# HPS_IOs.net
KiCad netlist of a schematic drawn in Altium Designer
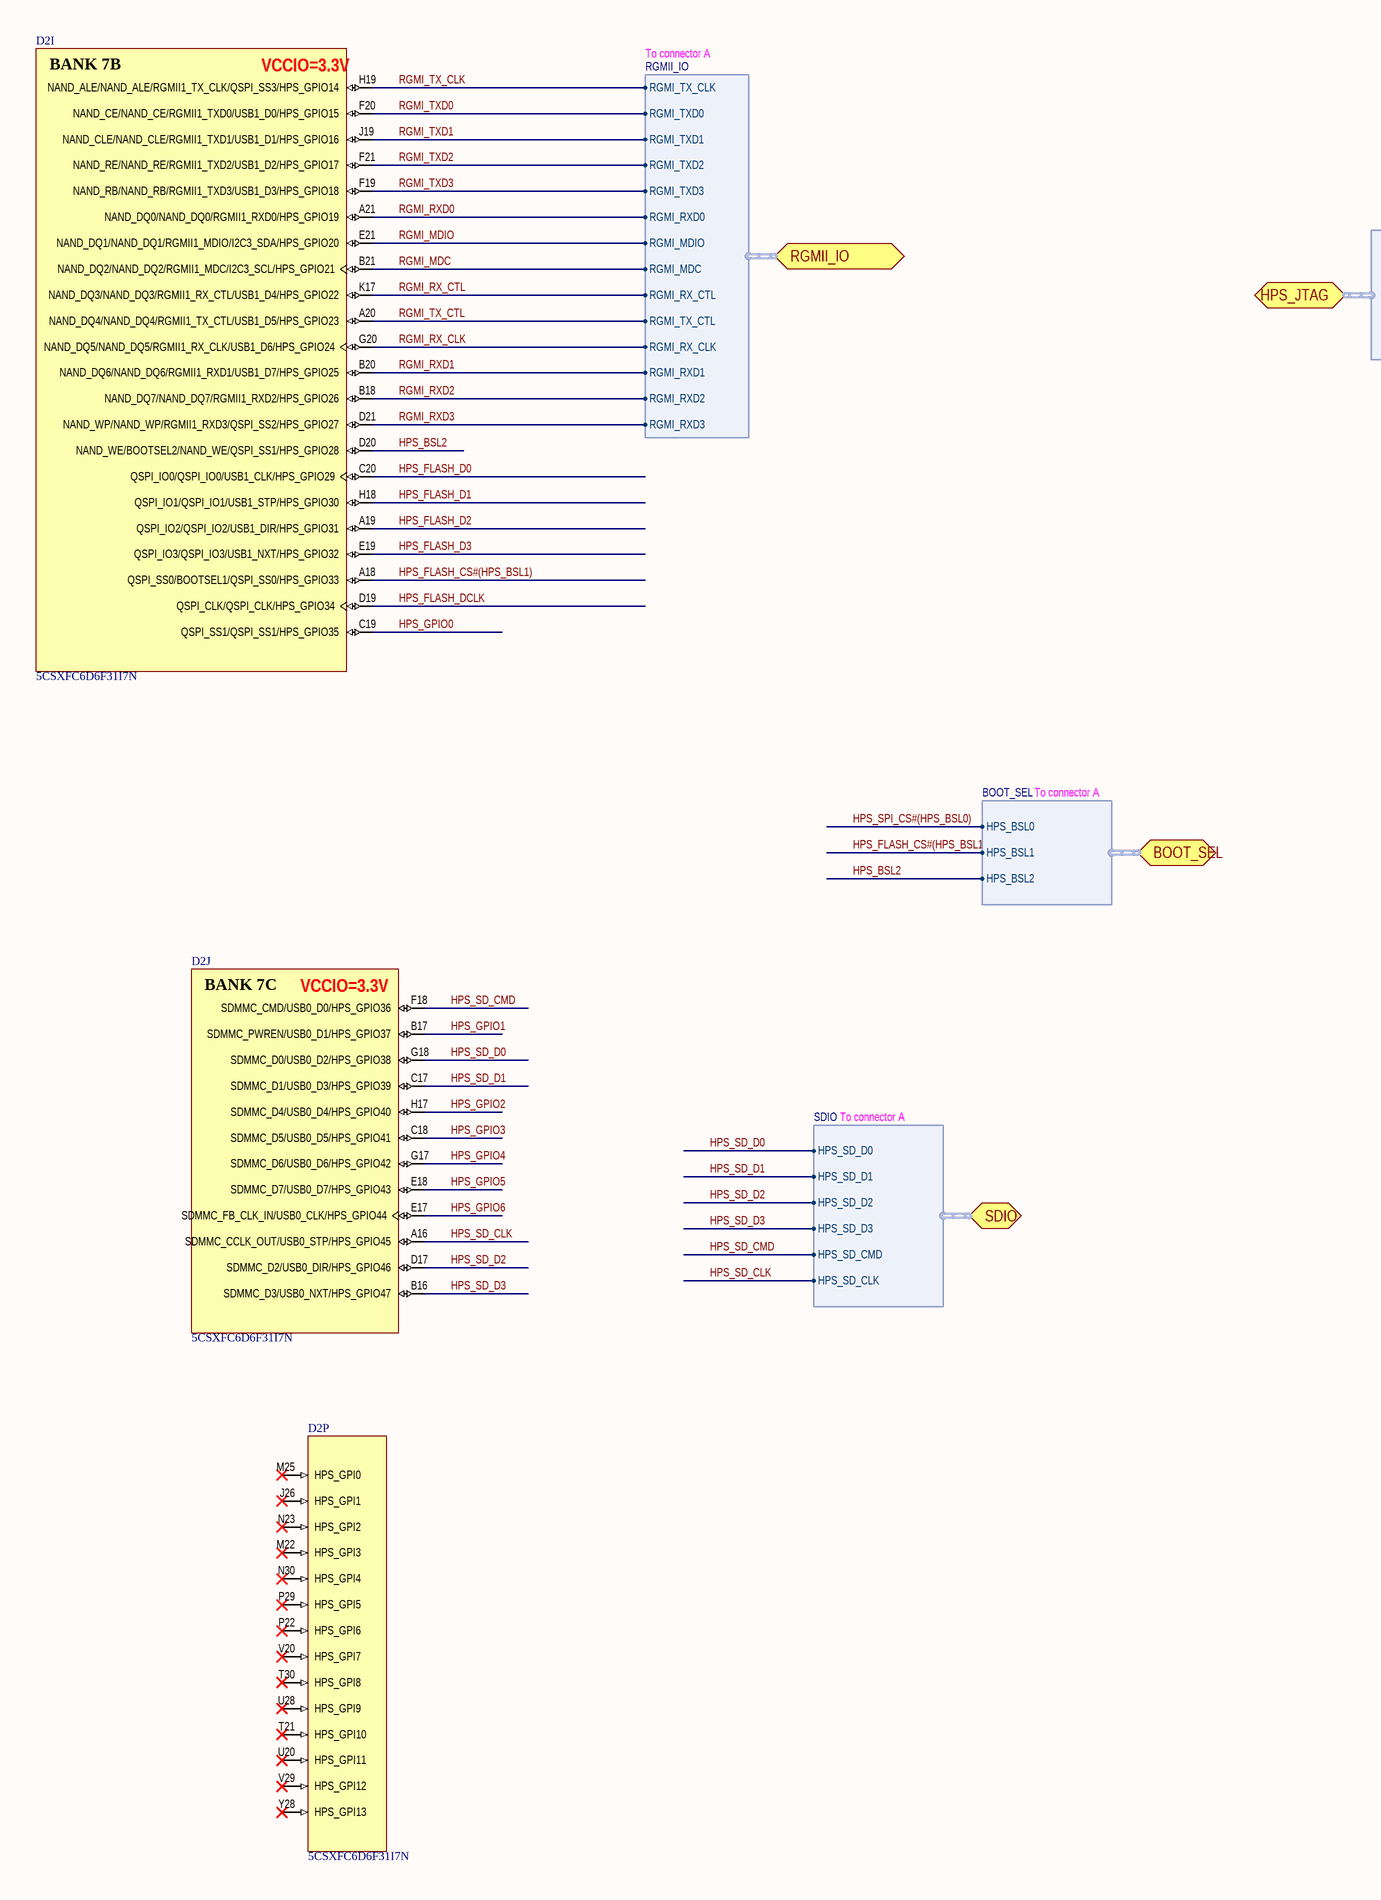
[diagram p0: HPS_IOs.SchDoc, left]
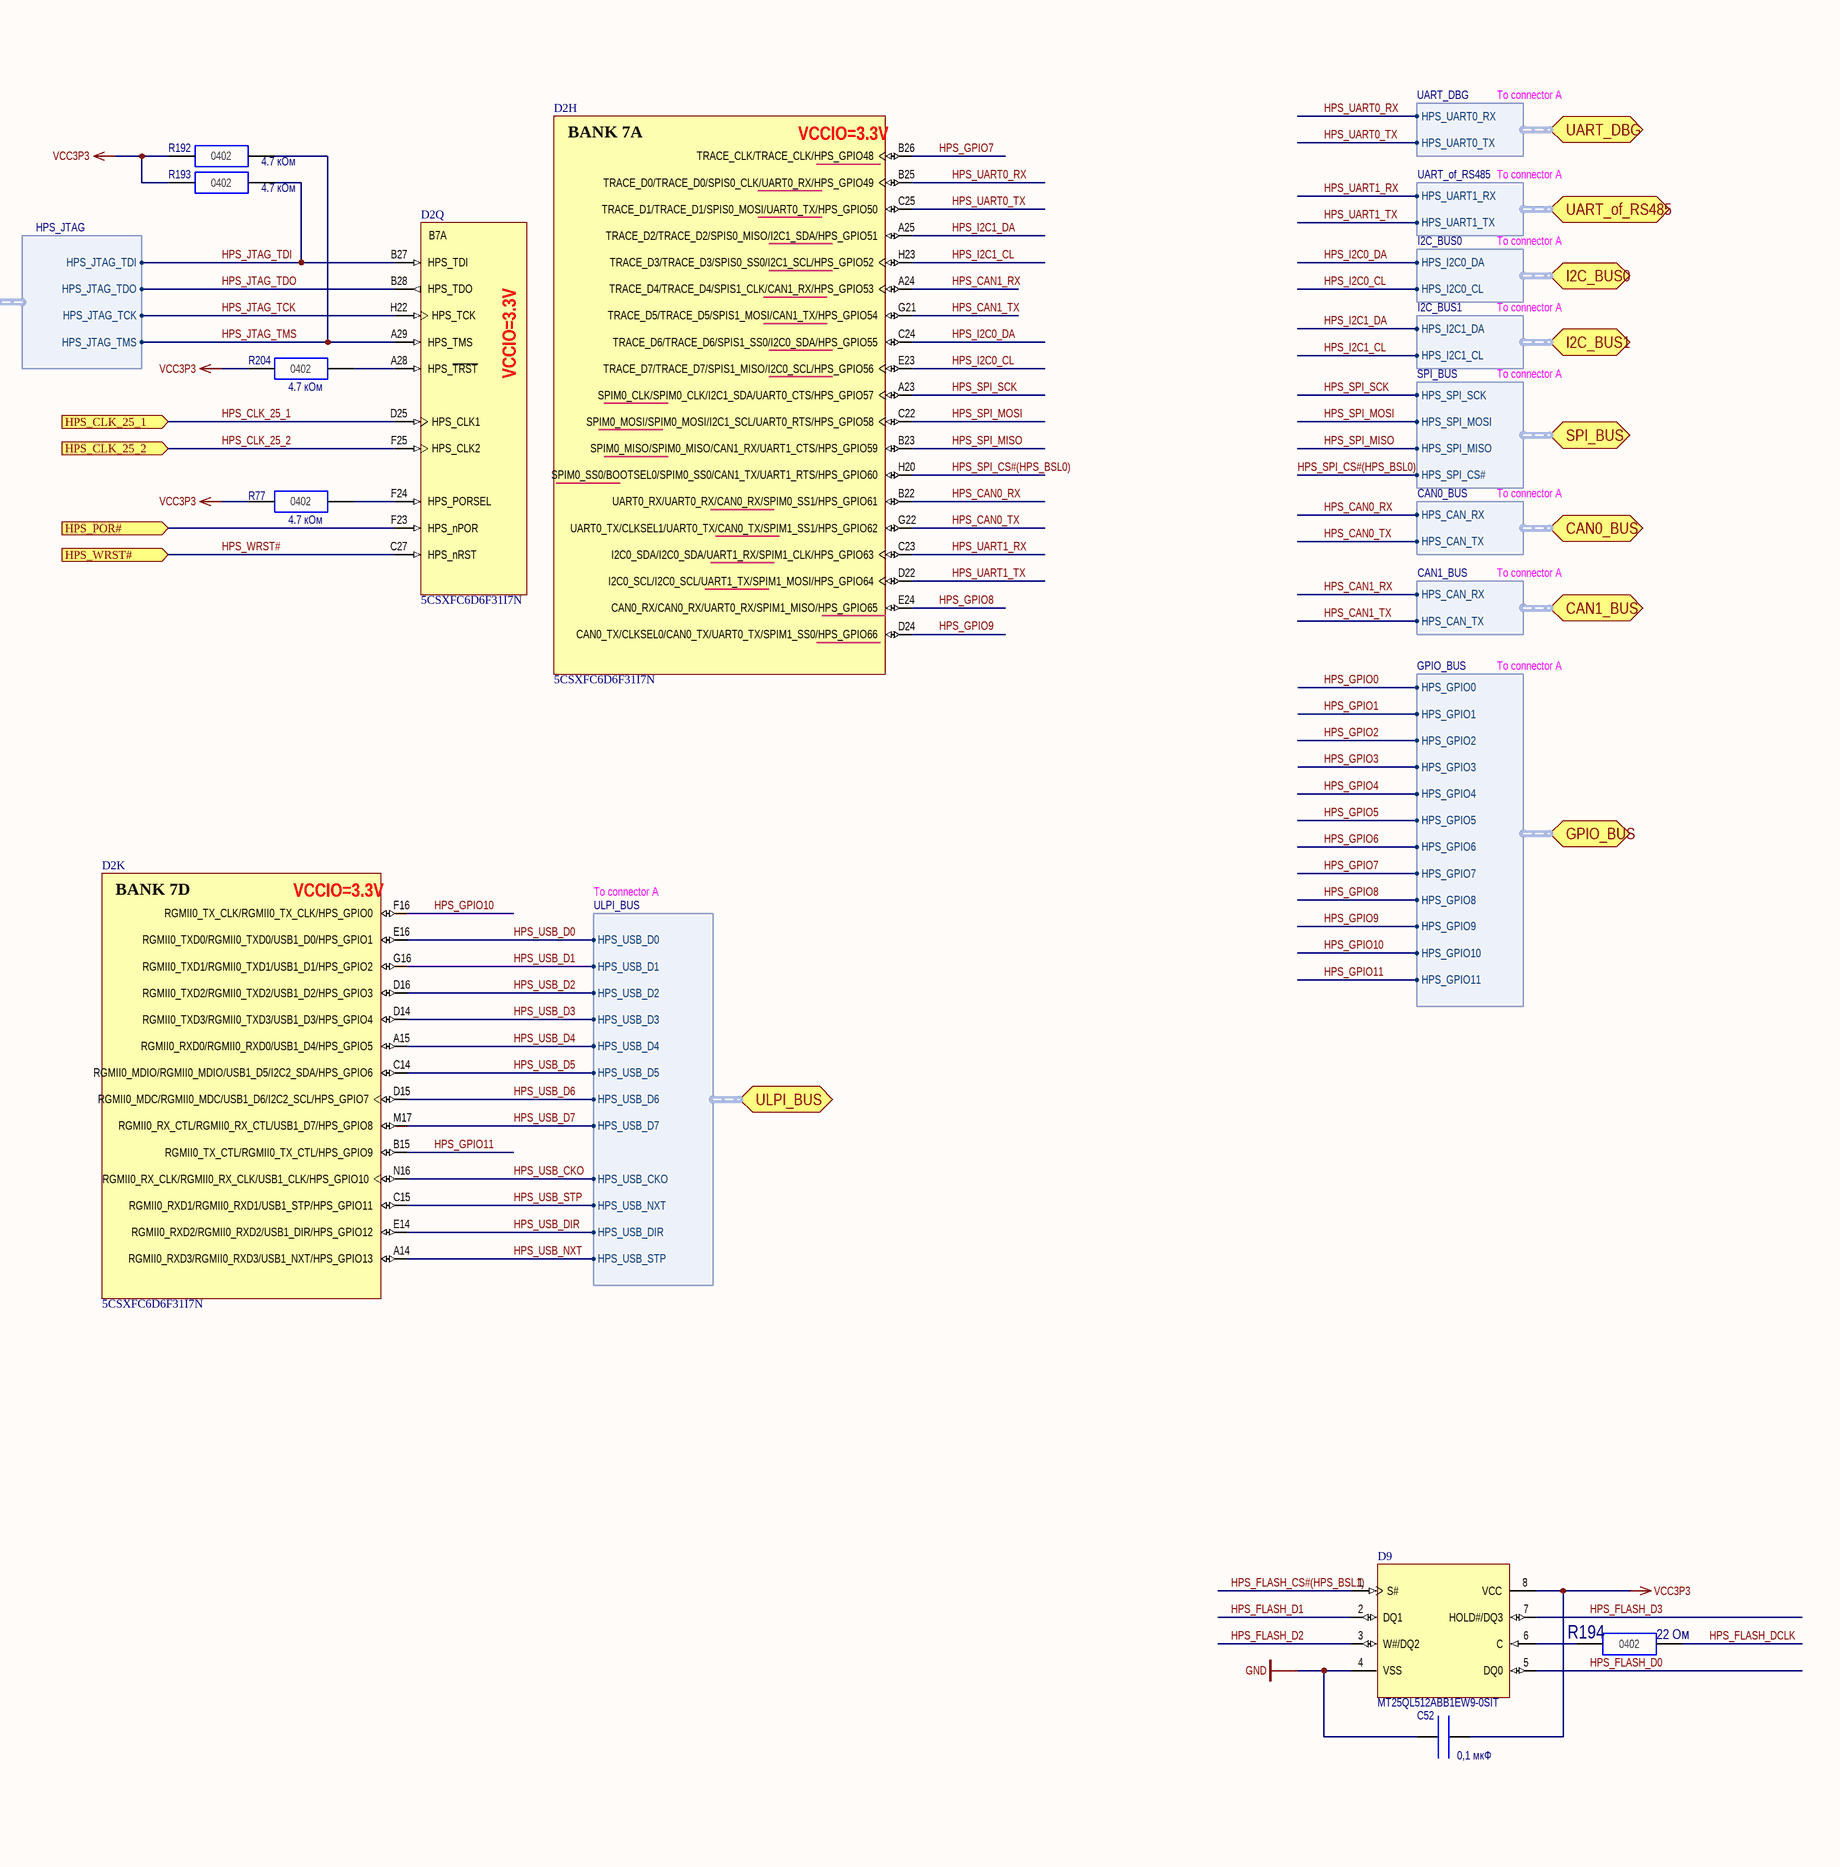
[diagram p1: HPS_IOs.SchDoc, right]

(export (version "E")
  (design (tool "Eeschema 10.0.6"))
  (components
    (comp (ref "C52")
      (value "0,1 мкФ")
      (footprint "CC0402(1005)")
      (description "Чип конденсатор керамический")
      (fields (field (name "Comment") "CC0402-X7R-0,1 мкФ-20%-10В"))
      (libsource (lib "Чип конденсаторы") (part "CC0402-X7R-#-20%-10В"))
    )
    (comp (ref "D2")
      (value "5CSXFC6D6F31I7N")
      (footprint "ALTR-FBGA896_A-200")
      (fields (field (name "MANUFACTURER") "Altera"))
      (libsource (lib "Altera Cyclone V_sd") (part "5CSXFC6D6F31I7N"))
    )
    (comp (ref "D9")
      (value "MT25QL512ABB1EW9-0SIT")
      (footprint "SON127P800X80_HS-9N")
      (fields (field (name "VOLTAGE") "2.7V-3.6V ") (field (name "MANUFACTURER") "Micron"))
      (libsource (lib "SD_IC") (part "MT25QL512ABB1EW9-0SIT"))
    )
    (comp (ref "R77")
      (value "4.7 кОм")
      (footprint "CR0402(1005)_OCT")
      (description "Чип резистор")
      (fields (field (name "TOLERANCE") "5%") (field (name "Comment") "CR0402-4.7 кОм-±5%"))
      (libsource (lib "Резисторы") (part "CR0402-#-±5%"))
    )
    (comp (ref "R192")
      (value "4.7 кОм")
      (footprint "CR0402(1005)")
      (description "Чип резистор")
      (fields (field (name "TOLERANCE") "5%") (field (name "Comment") "CR0402-4.7 кОм-±5%"))
      (libsource (lib "Резисторы") (part "CR0402-#-±5%"))
    )
    (comp (ref "R193")
      (value "4.7 кОм")
      (footprint "CR0402(1005)_OCT")
      (description "Чип резистор")
      (fields (field (name "TOLERANCE") "5%") (field (name "Comment") "CR0402-4.7 кОм-±5%"))
      (libsource (lib "Резисторы") (part "CR0402-#-±5%"))
    )
    (comp (ref "R194")
      (value "22 Ом")
      (footprint "CR0402(1005)")
      (description "Чип резистор")
      (fields (field (name "TOLERANCE") "5%") (field (name "Comment") "CR0402-22 Ом-±5%"))
      (libsource (lib "Чип резисторы") (part "CR0402-#-±5%"))
    )
    (comp (ref "R204")
      (value "4.7 кОм")
      (footprint "CR0402(1005)")
      (description "Чип резистор")
      (fields (field (name "TOLERANCE") "5%") (field (name "Comment") "CR0402-4.7 кОм-±5%"))
      (libsource (lib "Резисторы") (part "CR0402-#-±5%"))
    )
  )
  (nets
    (net (code "14") (name "/HPS_BSL2") (class "Default")
      (node (ref "D2") (pin "D20") (pinfunction "NAND_WE/BOOTSEL2/NAND_WE/QSPI_SS1/HPS_GPIO28_D20") (pintype "bidirectional"))
    )
    (net (code "15") (name "/HPS_CAN0_RX") (class "Default")
      (node (ref "D2") (pin "B22") (pinfunction "UART0_RX/UART0_RX/CAN0_RX/SPIM0_SS1/HPS_GPIO61_B22") (pintype "bidirectional"))
    )
    (net (code "16") (name "/HPS_CAN0_TX") (class "Default")
      (node (ref "D2") (pin "G22") (pinfunction "UART0_TX/CLKSEL1/UART0_TX/CAN0_TX/SPIM1_SS1/HPS_GPIO62_G22") (pintype "bidirectional"))
    )
    (net (code "17") (name "/HPS_CAN1_RX") (class "Default")
      (node (ref "D2") (pin "A24") (pinfunction "TRACE_D4/TRACE_D4/SPIS1_CLK/CAN1_RX/HPS_GPIO53_A24") (pintype "bidirectional"))
    )
    (net (code "18") (name "/HPS_CAN1_TX") (class "Default")
      (node (ref "D2") (pin "G21") (pinfunction "TRACE_D5/TRACE_D5/SPIS1_MOSI/CAN1_TX/HPS_GPIO54_G21") (pintype "bidirectional"))
    )
    (net (code "19") (name "/HPS_CLK_25_1") (class "Default")
      (node (ref "D2") (pin "D25") (pinfunction "HPS_CLK1_D25") (pintype "input"))
    )
    (net (code "20") (name "/HPS_CLK_25_2") (class "Default")
      (node (ref "D2") (pin "F25") (pinfunction "HPS_CLK2_F25") (pintype "input"))
    )
    (net (code "21") (name "/HPS_FLASH_CS#(HPS_BSL1)") (class "Default")
      (node (ref "D2") (pin "A18") (pinfunction "QSPI_SS0/BOOTSEL1/QSPI_SS0/HPS_GPIO33_A18") (pintype "bidirectional"))
      (node (ref "D9") (pin "1") (pinfunction "S#_1") (pintype "input"))
    )
    (net (code "22") (name "/HPS_FLASH_D0") (class "Default")
      (node (ref "D2") (pin "C20") (pinfunction "QSPI_IO0/QSPI_IO0/USB1_CLK/HPS_GPIO29_C20") (pintype "bidirectional"))
      (node (ref "D9") (pin "5") (pinfunction "DQ0_5") (pintype "bidirectional"))
    )
    (net (code "23") (name "/HPS_FLASH_D1") (class "Default")
      (node (ref "D2") (pin "H18") (pinfunction "QSPI_IO1/QSPI_IO1/USB1_STP/HPS_GPIO30_H18") (pintype "bidirectional"))
      (node (ref "D9") (pin "2") (pinfunction "DQ1_2") (pintype "bidirectional"))
    )
    (net (code "24") (name "/HPS_FLASH_D2") (class "Default")
      (node (ref "D2") (pin "A19") (pinfunction "QSPI_IO2/QSPI_IO2/USB1_DIR/HPS_GPIO31_A19") (pintype "bidirectional"))
      (node (ref "D9") (pin "3") (pinfunction "W#/DQ2_3") (pintype "bidirectional"))
    )
    (net (code "25") (name "/HPS_FLASH_D3") (class "Default")
      (node (ref "D2") (pin "E19") (pinfunction "QSPI_IO3/QSPI_IO3/USB1_NXT/HPS_GPIO32_E19") (pintype "bidirectional"))
      (node (ref "D9") (pin "7") (pinfunction "HOLD#/DQ3_7") (pintype "bidirectional"))
    )
    (net (code "26") (name "/HPS_FLASH_DCLK") (class "Default")
      (node (ref "D2") (pin "D19") (pinfunction "QSPI_CLK/QSPI_CLK/HPS_GPIO34_D19") (pintype "bidirectional"))
      (node (ref "R194") (pin "2") (pinfunction "-_2") (pintype "passive"))
    )
    (net (code "27") (name "/HPS_GPIO0") (class "Default")
      (node (ref "D2") (pin "C19") (pinfunction "QSPI_SS1/QSPI_SS1/HPS_GPIO35_C19") (pintype "bidirectional"))
    )
    (net (code "28") (name "/HPS_GPIO1") (class "Default")
      (node (ref "D2") (pin "B17") (pinfunction "SDMMC_PWREN/USB0_D1/HPS_GPIO37_B17") (pintype "bidirectional"))
    )
    (net (code "29") (name "/HPS_GPIO2") (class "Default")
      (node (ref "D2") (pin "H17") (pinfunction "SDMMC_D4/USB0_D4/HPS_GPIO40_H17") (pintype "bidirectional"))
    )
    (net (code "30") (name "/HPS_GPIO3") (class "Default")
      (node (ref "D2") (pin "C18") (pinfunction "SDMMC_D5/USB0_D5/HPS_GPIO41_C18") (pintype "bidirectional"))
    )
    (net (code "31") (name "/HPS_GPIO4") (class "Default")
      (node (ref "D2") (pin "G17") (pinfunction "SDMMC_D6/USB0_D6/HPS_GPIO42_G17") (pintype "bidirectional"))
    )
    (net (code "32") (name "/HPS_GPIO5") (class "Default")
      (node (ref "D2") (pin "E18") (pinfunction "SDMMC_D7/USB0_D7/HPS_GPIO43_E18") (pintype "bidirectional"))
    )
    (net (code "33") (name "/HPS_GPIO6") (class "Default")
      (node (ref "D2") (pin "E17") (pinfunction "SDMMC_FB_CLK_IN/USB0_CLK/HPS_GPIO44_E17") (pintype "bidirectional"))
    )
    (net (code "34") (name "/HPS_GPIO7") (class "Default")
      (node (ref "D2") (pin "B26") (pinfunction "TRACE_CLK/TRACE_CLK/HPS_GPIO48_B26") (pintype "bidirectional"))
    )
    (net (code "35") (name "/HPS_GPIO8") (class "Default")
      (node (ref "D2") (pin "E24") (pinfunction "CAN0_RX/CAN0_RX/UART0_RX/SPIM1_MISO/HPS_GPIO65_E24") (pintype "bidirectional"))
    )
    (net (code "36") (name "/HPS_GPIO9") (class "Default")
      (node (ref "D2") (pin "D24") (pinfunction "CAN0_TX/CLKSEL0/CAN0_TX/UART0_TX/SPIM1_SS0/HPS_GPIO66_D24") (pintype "bidirectional"))
    )
    (net (code "37") (name "/HPS_GPIO10") (class "Default")
      (node (ref "D2") (pin "F16") (pinfunction "RGMII0_TX_CLK/RGMII0_TX_CLK/HPS_GPIO0_F16") (pintype "bidirectional"))
    )
    (net (code "38") (name "/HPS_GPIO11") (class "Default")
      (node (ref "D2") (pin "B15") (pinfunction "RGMII0_TX_CTL/RGMII0_TX_CTL/HPS_GPIO9_B15") (pintype "bidirectional"))
    )
    (net (code "39") (name "/HPS_I2C0_CL") (class "Default")
      (node (ref "D2") (pin "E23") (pinfunction "TRACE_D7/TRACE_D7/SPIS1_MISO/I2C0_SCL/HPS_GPIO56_E23") (pintype "bidirectional"))
    )
    (net (code "40") (name "/HPS_I2C0_DA") (class "Default")
      (node (ref "D2") (pin "C24") (pinfunction "TRACE_D6/TRACE_D6/SPIS1_SS0/I2C0_SDA/HPS_GPIO55_C24") (pintype "bidirectional"))
    )
    (net (code "41") (name "/HPS_I2C1_CL") (class "Default")
      (node (ref "D2") (pin "H23") (pinfunction "TRACE_D3/TRACE_D3/SPIS0_SS0/I2C1_SCL/HPS_GPIO52_H23") (pintype "bidirectional"))
    )
    (net (code "42") (name "/HPS_I2C1_DA") (class "Default")
      (node (ref "D2") (pin "A25") (pinfunction "TRACE_D2/TRACE_D2/SPIS0_MISO/I2C1_SDA/HPS_GPIO51_A25") (pintype "bidirectional"))
    )
    (net (code "43") (name "/HPS_JTAG_TCK") (class "Default")
      (node (ref "D2") (pin "H22") (pinfunction "HPS_TCK_H22") (pintype "input"))
    )
    (net (code "44") (name "/HPS_JTAG_TDI") (class "Default")
      (node (ref "D2") (pin "B27") (pinfunction "HPS_TDI_B27") (pintype "input"))
      (node (ref "R193") (pin "2") (pinfunction "-_2") (pintype "passive"))
    )
    (net (code "45") (name "/HPS_JTAG_TDO") (class "Default")
      (node (ref "D2") (pin "B28") (pinfunction "HPS_TDO_B28") (pintype "output"))
    )
    (net (code "46") (name "/HPS_JTAG_TMS") (class "Default")
      (node (ref "D2") (pin "A29") (pinfunction "HPS_TMS_A29") (pintype "input"))
      (node (ref "R192") (pin "2") (pinfunction "-_2") (pintype "passive"))
    )
    (net (code "47") (name "/HPS_POR#") (class "Default")
      (node (ref "D2") (pin "F23") (pinfunction "HPS_nPOR_F23") (pintype "input"))
    )
    (net (code "48") (name "/HPS_SD_CLK") (class "Default")
      (node (ref "D2") (pin "A16") (pinfunction "SDMMC_CCLK_OUT/USB0_STP/HPS_GPIO45_A16") (pintype "bidirectional"))
    )
    (net (code "49") (name "/HPS_SD_CMD") (class "Default")
      (node (ref "D2") (pin "F18") (pinfunction "SDMMC_CMD/USB0_D0/HPS_GPIO36_F18") (pintype "bidirectional"))
    )
    (net (code "50") (name "/HPS_SD_D0") (class "Default")
      (node (ref "D2") (pin "G18") (pinfunction "SDMMC_D0/USB0_D2/HPS_GPIO38_G18") (pintype "bidirectional"))
    )
    (net (code "51") (name "/HPS_SD_D1") (class "Default")
      (node (ref "D2") (pin "C17") (pinfunction "SDMMC_D1/USB0_D3/HPS_GPIO39_C17") (pintype "bidirectional"))
    )
    (net (code "52") (name "/HPS_SD_D2") (class "Default")
      (node (ref "D2") (pin "D17") (pinfunction "SDMMC_D2/USB0_DIR/HPS_GPIO46_D17") (pintype "bidirectional"))
    )
    (net (code "53") (name "/HPS_SD_D3") (class "Default")
      (node (ref "D2") (pin "B16") (pinfunction "SDMMC_D3/USB0_NXT/HPS_GPIO47_B16") (pintype "bidirectional"))
    )
    (net (code "54") (name "/HPS_SPI_CS#(HPS_BSL0)") (class "Default")
      (node (ref "D2") (pin "H20") (pinfunction "SPIM0_SS0/BOOTSEL0/SPIM0_SS0/CAN1_TX/UART1_RTS/HPS_GPIO60_H20") (pintype "bidirectional"))
    )
    (net (code "55") (name "/HPS_SPI_MISO") (class "Default")
      (node (ref "D2") (pin "B23") (pinfunction "SPIM0_MISO/SPIM0_MISO/CAN1_RX/UART1_CTS/HPS_GPIO59_B23") (pintype "bidirectional"))
    )
    (net (code "56") (name "/HPS_SPI_MOSI") (class "Default")
      (node (ref "D2") (pin "C22") (pinfunction "SPIM0_MOSI/SPIM0_MOSI/I2C1_SCL/UART0_RTS/HPS_GPIO58_C22") (pintype "bidirectional"))
    )
    (net (code "57") (name "/HPS_SPI_SCK") (class "Default")
      (node (ref "D2") (pin "A23") (pinfunction "SPIM0_CLK/SPIM0_CLK/I2C1_SDA/UART0_CTS/HPS_GPIO57_A23") (pintype "bidirectional"))
    )
    (net (code "58") (name "/HPS_UART0_RX") (class "Default")
      (node (ref "D2") (pin "B25") (pinfunction "TRACE_D0/TRACE_D0/SPIS0_CLK/UART0_RX/HPS_GPIO49_B25") (pintype "bidirectional"))
    )
    (net (code "59") (name "/HPS_UART0_TX") (class "Default")
      (node (ref "D2") (pin "C25") (pinfunction "TRACE_D1/TRACE_D1/SPIS0_MOSI/UART0_TX/HPS_GPIO50_C25") (pintype "bidirectional"))
    )
    (net (code "60") (name "/HPS_UART1_RX") (class "Default")
      (node (ref "D2") (pin "C23") (pinfunction "I2C0_SDA/I2C0_SDA/UART1_RX/SPIM1_CLK/HPS_GPIO63_C23") (pintype "bidirectional"))
    )
    (net (code "61") (name "/HPS_UART1_TX") (class "Default")
      (node (ref "D2") (pin "D22") (pinfunction "I2C0_SCL/I2C0_SCL/UART1_TX/SPIM1_MOSI/HPS_GPIO64_D22") (pintype "bidirectional"))
    )
    (net (code "62") (name "/HPS_USB_CKO") (class "Default")
      (node (ref "D2") (pin "N16") (pinfunction "RGMII0_RX_CLK/RGMII0_RX_CLK/USB1_CLK/HPS_GPIO10_N16") (pintype "bidirectional"))
    )
    (net (code "63") (name "/HPS_USB_D0") (class "Default")
      (node (ref "D2") (pin "E16") (pinfunction "RGMII0_TXD0/RGMII0_TXD0/USB1_D0/HPS_GPIO1_E16") (pintype "bidirectional"))
    )
    (net (code "64") (name "/HPS_USB_D1") (class "Default")
      (node (ref "D2") (pin "G16") (pinfunction "RGMII0_TXD1/RGMII0_TXD1/USB1_D1/HPS_GPIO2_G16") (pintype "bidirectional"))
    )
    (net (code "65") (name "/HPS_USB_D2") (class "Default")
      (node (ref "D2") (pin "D16") (pinfunction "RGMII0_TXD2/RGMII0_TXD2/USB1_D2/HPS_GPIO3_D16") (pintype "bidirectional"))
    )
    (net (code "66") (name "/HPS_USB_D3") (class "Default")
      (node (ref "D2") (pin "D14") (pinfunction "RGMII0_TXD3/RGMII0_TXD3/USB1_D3/HPS_GPIO4_D14") (pintype "bidirectional"))
    )
    (net (code "67") (name "/HPS_USB_D4") (class "Default")
      (node (ref "D2") (pin "A15") (pinfunction "RGMII0_RXD0/RGMII0_RXD0/USB1_D4/HPS_GPIO5_A15") (pintype "bidirectional"))
    )
    (net (code "68") (name "/HPS_USB_D5") (class "Default")
      (node (ref "D2") (pin "C14") (pinfunction "RGMII0_MDIO/RGMII0_MDIO/USB1_D5/I2C2_SDA/HPS_GPIO6_C14") (pintype "bidirectional"))
    )
    (net (code "69") (name "/HPS_USB_D6") (class "Default")
      (node (ref "D2") (pin "D15") (pinfunction "RGMII0_MDC/RGMII0_MDC/USB1_D6/I2C2_SCL/HPS_GPIO7_D15") (pintype "bidirectional"))
    )
    (net (code "70") (name "/HPS_USB_D7") (class "Default")
      (node (ref "D2") (pin "M17") (pinfunction "RGMII0_RX_CTL/RGMII0_RX_CTL/USB1_D7/HPS_GPIO8_M17") (pintype "bidirectional"))
    )
    (net (code "71") (name "/HPS_USB_DIR") (class "Default")
      (node (ref "D2") (pin "E14") (pinfunction "RGMII0_RXD2/RGMII0_RXD2/USB1_DIR/HPS_GPIO12_E14") (pintype "bidirectional"))
    )
    (net (code "72") (name "/HPS_USB_NXT") (class "Default")
      (node (ref "D2") (pin "A14") (pinfunction "RGMII0_RXD3/RGMII0_RXD3/USB1_NXT/HPS_GPIO13_A14") (pintype "bidirectional"))
    )
    (net (code "73") (name "/HPS_USB_STP") (class "Default")
      (node (ref "D2") (pin "C15") (pinfunction "RGMII0_RXD1/RGMII0_RXD1/USB1_STP/HPS_GPIO11_C15") (pintype "bidirectional"))
    )
    (net (code "74") (name "/HPS_WRST#") (class "Default")
      (node (ref "D2") (pin "C27") (pinfunction "HPS_nRST_C27") (pintype "input"))
    )
    (net (code "75") (name "/RGMI_MDC") (class "Default")
      (node (ref "D2") (pin "B21") (pinfunction "NAND_DQ2/NAND_DQ2/RGMII1_MDC/I2C3_SCL/HPS_GPIO21_B21") (pintype "bidirectional"))
    )
    (net (code "76") (name "/RGMI_MDIO") (class "Default")
      (node (ref "D2") (pin "E21") (pinfunction "NAND_DQ1/NAND_DQ1/RGMII1_MDIO/I2C3_SDA/HPS_GPIO20_E21") (pintype "bidirectional"))
    )
    (net (code "77") (name "/RGMI_RXD0") (class "Default")
      (node (ref "D2") (pin "A21") (pinfunction "NAND_DQ0/NAND_DQ0/RGMII1_RXD0/HPS_GPIO19_A21") (pintype "bidirectional"))
    )
    (net (code "78") (name "/RGMI_RXD1") (class "Default")
      (node (ref "D2") (pin "B20") (pinfunction "NAND_DQ6/NAND_DQ6/RGMII1_RXD1/USB1_D7/HPS_GPIO25_B20") (pintype "bidirectional"))
    )
    (net (code "79") (name "/RGMI_RXD2") (class "Default")
      (node (ref "D2") (pin "B18") (pinfunction "NAND_DQ7/NAND_DQ7/RGMII1_RXD2/HPS_GPIO26_B18") (pintype "bidirectional"))
    )
    (net (code "80") (name "/RGMI_RXD3") (class "Default")
      (node (ref "D2") (pin "D21") (pinfunction "NAND_WP/NAND_WP/RGMII1_RXD3/QSPI_SS2/HPS_GPIO27_D21") (pintype "bidirectional"))
    )
    (net (code "81") (name "/RGMI_RX_CLK") (class "Default")
      (node (ref "D2") (pin "G20") (pinfunction "NAND_DQ5/NAND_DQ5/RGMII1_RX_CLK/USB1_D6/HPS_GPIO24_G20") (pintype "bidirectional"))
    )
    (net (code "82") (name "/RGMI_RX_CTL") (class "Default")
      (node (ref "D2") (pin "K17") (pinfunction "NAND_DQ3/NAND_DQ3/RGMII1_RX_CTL/USB1_D4/HPS_GPIO22_K17") (pintype "bidirectional"))
    )
    (net (code "83") (name "/RGMI_TXD0") (class "Default")
      (node (ref "D2") (pin "F20") (pinfunction "NAND_CE/NAND_CE/RGMII1_TXD0/USB1_D0/HPS_GPIO15_F20") (pintype "bidirectional"))
    )
    (net (code "84") (name "/RGMI_TXD1") (class "Default")
      (node (ref "D2") (pin "J19") (pinfunction "NAND_CLE/NAND_CLE/RGMII1_TXD1/USB1_D1/HPS_GPIO16_J19") (pintype "bidirectional"))
    )
    (net (code "85") (name "/RGMI_TXD2") (class "Default")
      (node (ref "D2") (pin "F21") (pinfunction "NAND_RE/NAND_RE/RGMII1_TXD2/USB1_D2/HPS_GPIO17_F21") (pintype "bidirectional"))
    )
    (net (code "86") (name "/RGMI_TXD3") (class "Default")
      (node (ref "D2") (pin "F19") (pinfunction "NAND_RB/NAND_RB/RGMII1_TXD3/USB1_D3/HPS_GPIO18_F19") (pintype "bidirectional"))
    )
    (net (code "87") (name "/RGMI_TX_CLK") (class "Default")
      (node (ref "D2") (pin "H19") (pinfunction "NAND_ALE/NAND_ALE/RGMII1_TX_CLK/QSPI_SS3/HPS_GPIO14_H19") (pintype "bidirectional"))
    )
    (net (code "88") (name "/RGMI_TX_CTL") (class "Default")
      (node (ref "D2") (pin "A20") (pinfunction "NAND_DQ4/NAND_DQ4/RGMII1_TX_CTL/USB1_D5/HPS_GPIO23_A20") (pintype "bidirectional"))
    )
    (net (code "102") (name "GND") (class "Default")
      (node (ref "C52") (pin "1") (pinfunction "+_1") (pintype "passive"))
      (node (ref "D9") (pin "4") (pinfunction "VSS_4") (pintype "power_in"))
    )
    (net (code "103") (name "Net-(D2Q-HPS_PORSEL)") (class "Default")
      (node (ref "D2") (pin "F24") (pinfunction "HPS_PORSEL_F24") (pintype "input"))
      (node (ref "R77") (pin "2") (pinfunction "-_2") (pintype "passive"))
    )
    (net (code "104") (name "Net-(D2Q-HPS_~{TRST})") (class "Default")
      (node (ref "D2") (pin "A28") (pinfunction "HPS_~{TRST}_A28") (pintype "input"))
      (node (ref "R204") (pin "2") (pinfunction "-_2") (pintype "passive"))
    )
    (net (code "105") (name "Net-(D9-C)") (class "Default")
      (node (ref "D9") (pin "6") (pinfunction "C_6") (pintype "input"))
      (node (ref "R194") (pin "1") (pinfunction "+_1") (pintype "passive"))
    )
    (net (code "106") (name "VCC3P3") (class "Default")
      (node (ref "C52") (pin "2") (pinfunction "-_2") (pintype "passive"))
      (node (ref "D9") (pin "8") (pinfunction "VCC_8") (pintype "power_in"))
      (node (ref "R192") (pin "1") (pinfunction "+_1") (pintype "passive"))
      (node (ref "R193") (pin "1") (pinfunction "+_1") (pintype "passive"))
      (node (ref "R204") (pin "1") (pinfunction "+_1") (pintype "passive"))
      (node (ref "R77") (pin "1") (pinfunction "+_1") (pintype "passive"))
    )
    (net (code "107") (name "unconnected-(D2P-HPS_GPI0-PadM25)") (class "Default")
      (node (ref "D2") (pin "M25") (pinfunction "HPS_GPI0_M25") (pintype "input+no_connect"))
    )
    (net (code "108") (name "unconnected-(D2P-HPS_GPI1-PadJ26)") (class "Default")
      (node (ref "D2") (pin "J26") (pinfunction "HPS_GPI1_J26") (pintype "input+no_connect"))
    )
    (net (code "109") (name "unconnected-(D2P-HPS_GPI2-PadN23)") (class "Default")
      (node (ref "D2") (pin "N23") (pinfunction "HPS_GPI2_N23") (pintype "input+no_connect"))
    )
    (net (code "110") (name "unconnected-(D2P-HPS_GPI3-PadM22)") (class "Default")
      (node (ref "D2") (pin "M22") (pinfunction "HPS_GPI3_M22") (pintype "input+no_connect"))
    )
    (net (code "111") (name "unconnected-(D2P-HPS_GPI4-PadN30)") (class "Default")
      (node (ref "D2") (pin "N30") (pinfunction "HPS_GPI4_N30") (pintype "input+no_connect"))
    )
    (net (code "112") (name "unconnected-(D2P-HPS_GPI5-PadP29)") (class "Default")
      (node (ref "D2") (pin "P29") (pinfunction "HPS_GPI5_P29") (pintype "input+no_connect"))
    )
    (net (code "113") (name "unconnected-(D2P-HPS_GPI6-PadP22)") (class "Default")
      (node (ref "D2") (pin "P22") (pinfunction "HPS_GPI6_P22") (pintype "input+no_connect"))
    )
    (net (code "114") (name "unconnected-(D2P-HPS_GPI7-PadV20)") (class "Default")
      (node (ref "D2") (pin "V20") (pinfunction "HPS_GPI7_V20") (pintype "input+no_connect"))
    )
    (net (code "115") (name "unconnected-(D2P-HPS_GPI8-PadT30)") (class "Default")
      (node (ref "D2") (pin "T30") (pinfunction "HPS_GPI8_T30") (pintype "input+no_connect"))
    )
    (net (code "116") (name "unconnected-(D2P-HPS_GPI9-PadU28)") (class "Default")
      (node (ref "D2") (pin "U28") (pinfunction "HPS_GPI9_U28") (pintype "input+no_connect"))
    )
    (net (code "117") (name "unconnected-(D2P-HPS_GPI10-PadT21)") (class "Default")
      (node (ref "D2") (pin "T21") (pinfunction "HPS_GPI10_T21") (pintype "input+no_connect"))
    )
    (net (code "118") (name "unconnected-(D2P-HPS_GPI11-PadU20)") (class "Default")
      (node (ref "D2") (pin "U20") (pinfunction "HPS_GPI11_U20") (pintype "input+no_connect"))
    )
    (net (code "119") (name "unconnected-(D2P-HPS_GPI12-PadV29)") (class "Default")
      (node (ref "D2") (pin "V29") (pinfunction "HPS_GPI12_V29") (pintype "input+no_connect"))
    )
    (net (code "120") (name "unconnected-(D2P-HPS_GPI13-PadY28)") (class "Default")
      (node (ref "D2") (pin "Y28") (pinfunction "HPS_GPI13_Y28") (pintype "input+no_connect"))
    )
  )
)
